# DigitalClockController.net
KiCad netlist of a schematic drawn in EAGLE
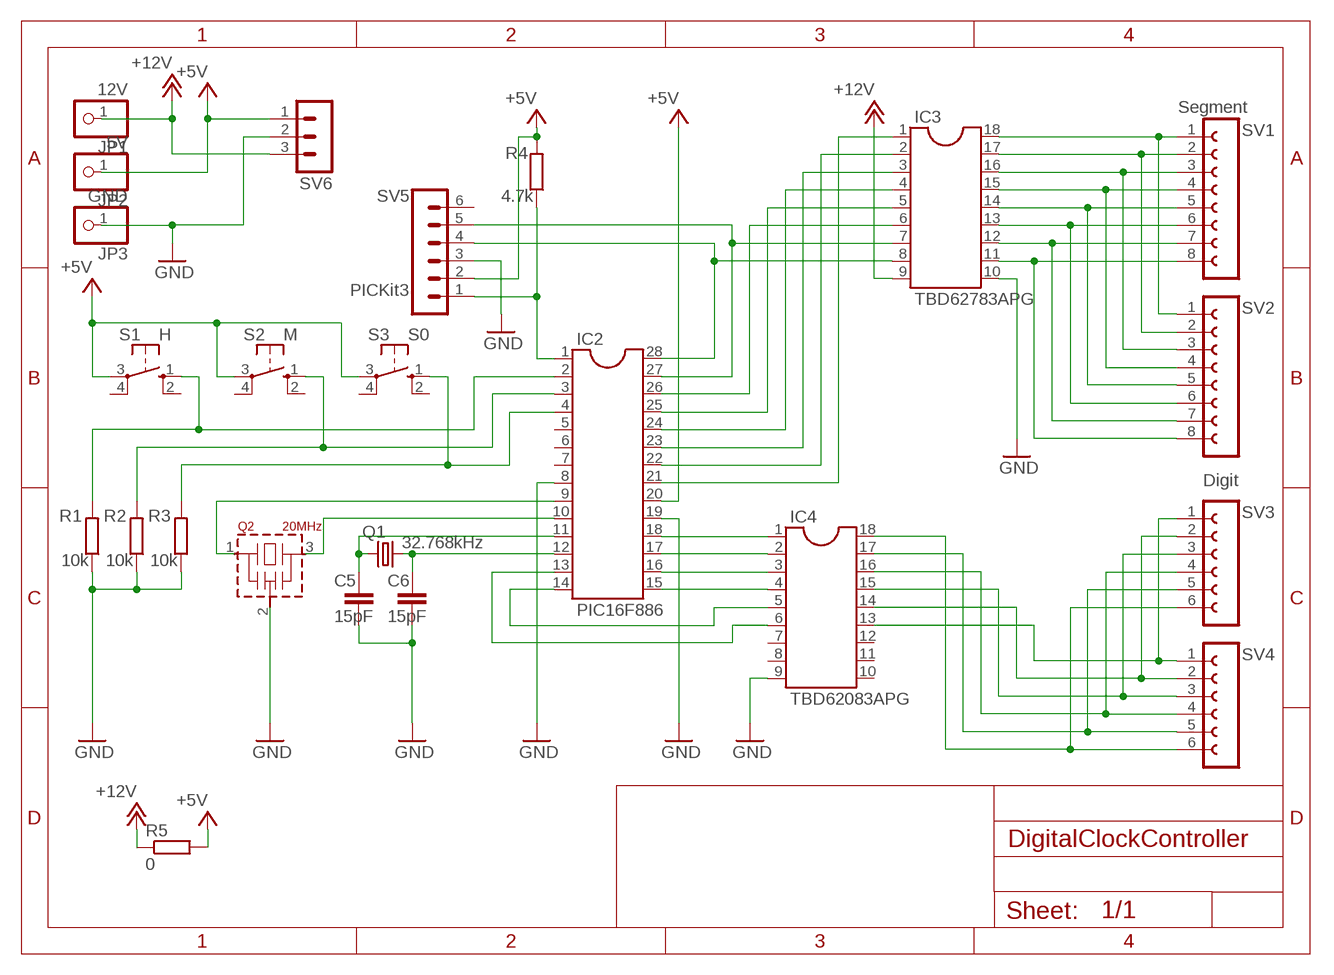
[diagram p0: schematic, sheet 1]

(export (version "E")
  (design (tool "Eeschema 10.0.6"))
  (components
    (comp (ref "C5")
      (value "15pF")
      (footprint "eagle-import:C025-024X044")
      (libsource (lib "eagle-import") (part "C-EU025-024X044"))
    )
    (comp (ref "C6")
      (value "15pF")
      (footprint "eagle-import:C025-024X044")
      (libsource (lib "eagle-import") (part "C-EU025-024X044"))
    )
    (comp (ref "IC2")
      (value "PIC16F886")
      (footprint "eagle-import:DIL28-3")
      (libsource (lib "eagle-import") (part "DIL28-3"))
    )
    (comp (ref "IC3")
      (value "TBD62783APG")
      (footprint "eagle-import:DIL18")
      (libsource (lib "eagle-import") (part "DIL18"))
    )
    (comp (ref "IC4")
      (value "TBD62083APG")
      (footprint "eagle-import:DIL18")
      (libsource (lib "eagle-import") (part "DIL18"))
    )
    (comp (ref "JP1")
      (value "12V")
      (footprint "eagle-import:1X01")
      (libsource (lib "eagle-import") (part "PINHD-1X1"))
    )
    (comp (ref "JP2")
      (value "5V")
      (footprint "eagle-import:1X01")
      (libsource (lib "eagle-import") (part "PINHD-1X1"))
    )
    (comp (ref "JP3")
      (value "GND")
      (footprint "eagle-import:1X01")
      (libsource (lib "eagle-import") (part "PINHD-1X1"))
    )
    (comp (ref "Q1")
      (value "32.768kHz")
      (footprint "eagle-import:TC26H")
      (libsource (lib "eagle-import") (part "CRYSTALTC26H"))
    )
    (comp (ref "Q2")
      (value "20MHz")
      (footprint "eagle-import:CSTLS_X")
      (libsource (lib "eagle-import") (part "CSTLS_X"))
    )
    (comp (ref "R1")
      (value "10k")
      (footprint "eagle-import:0207_10")
      (libsource (lib "eagle-import") (part "R-EU_0207/10"))
    )
    (comp (ref "R2")
      (value "10k")
      (footprint "eagle-import:0207_10")
      (libsource (lib "eagle-import") (part "R-EU_0207/10"))
    )
    (comp (ref "R3")
      (value "10k")
      (footprint "eagle-import:0207_10")
      (libsource (lib "eagle-import") (part "R-EU_0207/10"))
    )
    (comp (ref "R4")
      (value "4.7k")
      (footprint "eagle-import:0207_10")
      (libsource (lib "eagle-import") (part "R-EU_0207/10"))
    )
    (comp (ref "R5")
      (value "0")
      (footprint "eagle-import:0207_10")
      (libsource (lib "eagle-import") (part "R-EU_0207/10"))
    )
    (comp (ref "S1")
      (value "H")
      (footprint "eagle-import:B3F-10XX")
      (fields (field (name "MPN") "B3F-1000"))
      (libsource (lib "eagle-import") (part "10-XX"))
    )
    (comp (ref "S2")
      (value "M")
      (footprint "eagle-import:B3F-10XX")
      (fields (field (name "MPN") "B3F-1000"))
      (libsource (lib "eagle-import") (part "10-XX"))
    )
    (comp (ref "S3")
      (value "S0")
      (footprint "eagle-import:B3F-10XX")
      (fields (field (name "MPN") "B3F-1000"))
      (libsource (lib "eagle-import") (part "10-XX"))
    )
    (comp (ref "SV1")
      (value "Segment")
      (footprint "eagle-import:FE08")
      (libsource (lib "eagle-import") (part "FE08-1"))
    )
    (comp (ref "SV2")
      (value "Segment")
      (footprint "eagle-import:FE08")
      (libsource (lib "eagle-import") (part "FE08-1"))
    )
    (comp (ref "SV3")
      (value "Digit")
      (footprint "eagle-import:FE06")
      (libsource (lib "eagle-import") (part "FE06-1"))
    )
    (comp (ref "SV4")
      (value "Digit")
      (footprint "eagle-import:FE06")
      (libsource (lib "eagle-import") (part "FE06-1"))
    )
    (comp (ref "SV5")
      (value "PICKit3")
      (footprint "eagle-import:MA06-1")
      (libsource (lib "eagle-import") (part "MA06-1"))
    )
    (comp (ref "SV6")
      (value "MA03-1")
      (footprint "eagle-import:MA03-1")
      (libsource (lib "eagle-import") (part "MA03-1"))
    )
  )
  (nets
    (net (code "1") (name "+5V") (class "Default")
      (node (ref "IC2") (pin "20") (pinfunction "20_20") (pintype "passive"))
      (node (ref "JP2") (pin "1") (pinfunction "1_1") (pintype "passive"))
      (node (ref "R4") (pin "2") (pinfunction "2_2") (pintype "passive"))
      (node (ref "R5") (pin "2") (pinfunction "2_2") (pintype "passive"))
      (node (ref "S1") (pin "3") (pinfunction "P_3") (pintype "passive"))
      (node (ref "S2") (pin "3") (pinfunction "P_3") (pintype "passive"))
      (node (ref "S3") (pin "3") (pinfunction "P_3") (pintype "passive"))
      (node (ref "SV5") (pin "2") (pinfunction "2_2") (pintype "passive"))
      (node (ref "SV6") (pin "1") (pinfunction "1_1") (pintype "passive"))
    )
    (net (code "2") (name "+12V") (class "Default")
      (node (ref "IC3") (pin "9") (pinfunction "9_9") (pintype "passive"))
      (node (ref "JP1") (pin "1") (pinfunction "1_1") (pintype "passive"))
      (node (ref "R5") (pin "1") (pinfunction "1_1") (pintype "passive"))
      (node (ref "SV6") (pin "3") (pinfunction "3_3") (pintype "passive"))
    )
    (net (code "3") (name "GND") (class "Default")
      (node (ref "C5") (pin "2") (pinfunction "2_2") (pintype "passive"))
      (node (ref "C6") (pin "2") (pinfunction "2_2") (pintype "passive"))
      (node (ref "IC2") (pin "19") (pinfunction "19_19") (pintype "passive"))
      (node (ref "IC2") (pin "8") (pinfunction "8_8") (pintype "passive"))
      (node (ref "IC3") (pin "10") (pinfunction "10_10") (pintype "passive"))
      (node (ref "IC4") (pin "9") (pinfunction "9_9") (pintype "passive"))
      (node (ref "JP3") (pin "1") (pinfunction "1_1") (pintype "passive"))
      (node (ref "Q2") (pin "2") (pinfunction "VSS_2") (pintype "power_in"))
      (node (ref "R1") (pin "1") (pinfunction "1_1") (pintype "passive"))
      (node (ref "R2") (pin "1") (pinfunction "1_1") (pintype "passive"))
      (node (ref "R3") (pin "1") (pinfunction "1_1") (pintype "passive"))
      (node (ref "SV5") (pin "3") (pinfunction "3_3") (pintype "passive"))
      (node (ref "SV6") (pin "2") (pinfunction "2_2") (pintype "passive"))
    )
    (net (code "4") (name "Net-(C5-Pad1)") (class "Default")
      (node (ref "C5") (pin "1") (pinfunction "1_1") (pintype "passive"))
      (node (ref "IC2") (pin "11") (pinfunction "11_11") (pintype "passive"))
      (node (ref "Q1") (pin "2") (pinfunction "2_2") (pintype "passive"))
    )
    (net (code "5") (name "Net-(C6-Pad1)") (class "Default")
      (node (ref "C6") (pin "1") (pinfunction "1_1") (pintype "passive"))
      (node (ref "IC2") (pin "12") (pinfunction "12_12") (pintype "passive"))
      (node (ref "Q1") (pin "1") (pinfunction "1_1") (pintype "passive"))
    )
    (net (code "6") (name "Net-(IC2-Pad1)") (class "Default")
      (node (ref "IC2") (pin "1") (pinfunction "1_1") (pintype "passive"))
      (node (ref "R4") (pin "1") (pinfunction "1_1") (pintype "passive"))
      (node (ref "SV5") (pin "1") (pinfunction "1_1") (pintype "passive"))
    )
    (net (code "7") (name "Net-(IC2-Pad9)") (class "Default")
      (node (ref "IC2") (pin "9") (pinfunction "9_9") (pintype "passive"))
      (node (ref "Q2") (pin "1") (pinfunction "1_1") (pintype "output"))
    )
    (net (code "8") (name "Net-(IC2-Pad10)") (class "Default")
      (node (ref "IC2") (pin "10") (pinfunction "10_10") (pintype "passive"))
      (node (ref "Q2") (pin "3") (pinfunction "3_3") (pintype "input"))
    )
    (net (code "9") (name "Net-(IC2-Pad13)") (class "Default")
      (node (ref "IC2") (pin "13") (pinfunction "13_13") (pintype "passive"))
      (node (ref "IC4") (pin "6") (pinfunction "6_6") (pintype "passive"))
    )
    (net (code "10") (name "Net-(IC2-Pad14)") (class "Default")
      (node (ref "IC2") (pin "14") (pinfunction "14_14") (pintype "passive"))
      (node (ref "IC4") (pin "5") (pinfunction "5_5") (pintype "passive"))
    )
    (net (code "11") (name "Net-(IC2-Pad15)") (class "Default")
      (node (ref "IC2") (pin "15") (pinfunction "15_15") (pintype "passive"))
      (node (ref "IC4") (pin "4") (pinfunction "4_4") (pintype "passive"))
    )
    (net (code "12") (name "Net-(IC2-Pad16)") (class "Default")
      (node (ref "IC2") (pin "16") (pinfunction "16_16") (pintype "passive"))
      (node (ref "IC4") (pin "3") (pinfunction "3_3") (pintype "passive"))
    )
    (net (code "13") (name "Net-(IC2-Pad17)") (class "Default")
      (node (ref "IC2") (pin "17") (pinfunction "17_17") (pintype "passive"))
      (node (ref "IC4") (pin "2") (pinfunction "2_2") (pintype "passive"))
    )
    (net (code "14") (name "Net-(IC2-Pad18)") (class "Default")
      (node (ref "IC2") (pin "18") (pinfunction "18_18") (pintype "passive"))
      (node (ref "IC4") (pin "1") (pinfunction "1_1") (pintype "passive"))
    )
    (net (code "15") (name "Net-(IC2-Pad21)") (class "Default")
      (node (ref "IC2") (pin "21") (pinfunction "21_21") (pintype "passive"))
      (node (ref "IC3") (pin "1") (pinfunction "1_1") (pintype "passive"))
    )
    (net (code "16") (name "Net-(IC2-Pad22)") (class "Default")
      (node (ref "IC2") (pin "22") (pinfunction "22_22") (pintype "passive"))
      (node (ref "IC3") (pin "2") (pinfunction "2_2") (pintype "passive"))
    )
    (net (code "17") (name "Net-(IC2-Pad23)") (class "Default")
      (node (ref "IC2") (pin "23") (pinfunction "23_23") (pintype "passive"))
      (node (ref "IC3") (pin "3") (pinfunction "3_3") (pintype "passive"))
    )
    (net (code "18") (name "Net-(IC2-Pad24)") (class "Default")
      (node (ref "IC2") (pin "24") (pinfunction "24_24") (pintype "passive"))
      (node (ref "IC3") (pin "4") (pinfunction "4_4") (pintype "passive"))
    )
    (net (code "19") (name "Net-(IC2-Pad25)") (class "Default")
      (node (ref "IC2") (pin "25") (pinfunction "25_25") (pintype "passive"))
      (node (ref "IC3") (pin "5") (pinfunction "5_5") (pintype "passive"))
    )
    (net (code "20") (name "Net-(IC2-Pad26)") (class "Default")
      (node (ref "IC2") (pin "26") (pinfunction "26_26") (pintype "passive"))
      (node (ref "IC3") (pin "6") (pinfunction "6_6") (pintype "passive"))
    )
    (net (code "21") (name "Net-(IC2-Pad27)") (class "Default")
      (node (ref "IC2") (pin "27") (pinfunction "27_27") (pintype "passive"))
      (node (ref "IC3") (pin "7") (pinfunction "7_7") (pintype "passive"))
      (node (ref "SV5") (pin "5") (pinfunction "5_5") (pintype "passive"))
    )
    (net (code "22") (name "Net-(IC2-Pad28)") (class "Default")
      (node (ref "IC2") (pin "28") (pinfunction "28_28") (pintype "passive"))
      (node (ref "IC3") (pin "8") (pinfunction "8_8") (pintype "passive"))
      (node (ref "SV5") (pin "4") (pinfunction "4_4") (pintype "passive"))
    )
    (net (code "23") (name "Net-(IC3-Pad11)") (class "Default")
      (node (ref "IC3") (pin "11") (pinfunction "11_11") (pintype "passive"))
      (node (ref "SV1") (pin "8") (pinfunction "8_8") (pintype "passive"))
      (node (ref "SV2") (pin "8") (pinfunction "8_8") (pintype "passive"))
    )
    (net (code "24") (name "Net-(IC3-Pad12)") (class "Default")
      (node (ref "IC3") (pin "12") (pinfunction "12_12") (pintype "passive"))
      (node (ref "SV1") (pin "7") (pinfunction "7_7") (pintype "passive"))
      (node (ref "SV2") (pin "7") (pinfunction "7_7") (pintype "passive"))
    )
    (net (code "25") (name "Net-(IC3-Pad13)") (class "Default")
      (node (ref "IC3") (pin "13") (pinfunction "13_13") (pintype "passive"))
      (node (ref "SV1") (pin "6") (pinfunction "6_6") (pintype "passive"))
      (node (ref "SV2") (pin "6") (pinfunction "6_6") (pintype "passive"))
    )
    (net (code "26") (name "Net-(IC3-Pad14)") (class "Default")
      (node (ref "IC3") (pin "14") (pinfunction "14_14") (pintype "passive"))
      (node (ref "SV1") (pin "5") (pinfunction "5_5") (pintype "passive"))
      (node (ref "SV2") (pin "5") (pinfunction "5_5") (pintype "passive"))
    )
    (net (code "27") (name "Net-(IC3-Pad15)") (class "Default")
      (node (ref "IC3") (pin "15") (pinfunction "15_15") (pintype "passive"))
      (node (ref "SV1") (pin "4") (pinfunction "4_4") (pintype "passive"))
      (node (ref "SV2") (pin "4") (pinfunction "4_4") (pintype "passive"))
    )
    (net (code "28") (name "Net-(IC3-Pad16)") (class "Default")
      (node (ref "IC3") (pin "16") (pinfunction "16_16") (pintype "passive"))
      (node (ref "SV1") (pin "3") (pinfunction "3_3") (pintype "passive"))
      (node (ref "SV2") (pin "3") (pinfunction "3_3") (pintype "passive"))
    )
    (net (code "29") (name "Net-(IC3-Pad17)") (class "Default")
      (node (ref "IC3") (pin "17") (pinfunction "17_17") (pintype "passive"))
      (node (ref "SV1") (pin "2") (pinfunction "2_2") (pintype "passive"))
      (node (ref "SV2") (pin "2") (pinfunction "2_2") (pintype "passive"))
    )
    (net (code "30") (name "Net-(IC3-Pad18)") (class "Default")
      (node (ref "IC3") (pin "18") (pinfunction "18_18") (pintype "passive"))
      (node (ref "SV1") (pin "1") (pinfunction "1_1") (pintype "passive"))
      (node (ref "SV2") (pin "1") (pinfunction "1_1") (pintype "passive"))
    )
    (net (code "31") (name "Net-(IC4-Pad13)") (class "Default")
      (node (ref "IC4") (pin "13") (pinfunction "13_13") (pintype "passive"))
      (node (ref "SV3") (pin "1") (pinfunction "1_1") (pintype "passive"))
      (node (ref "SV4") (pin "1") (pinfunction "1_1") (pintype "passive"))
    )
    (net (code "32") (name "Net-(IC4-Pad14)") (class "Default")
      (node (ref "IC4") (pin "14") (pinfunction "14_14") (pintype "passive"))
      (node (ref "SV3") (pin "2") (pinfunction "2_2") (pintype "passive"))
      (node (ref "SV4") (pin "2") (pinfunction "2_2") (pintype "passive"))
    )
    (net (code "33") (name "Net-(IC4-Pad15)") (class "Default")
      (node (ref "IC4") (pin "15") (pinfunction "15_15") (pintype "passive"))
      (node (ref "SV3") (pin "3") (pinfunction "3_3") (pintype "passive"))
      (node (ref "SV4") (pin "3") (pinfunction "3_3") (pintype "passive"))
    )
    (net (code "34") (name "Net-(IC4-Pad16)") (class "Default")
      (node (ref "IC4") (pin "16") (pinfunction "16_16") (pintype "passive"))
      (node (ref "SV3") (pin "4") (pinfunction "4_4") (pintype "passive"))
      (node (ref "SV4") (pin "4") (pinfunction "4_4") (pintype "passive"))
    )
    (net (code "35") (name "Net-(IC4-Pad17)") (class "Default")
      (node (ref "IC4") (pin "17") (pinfunction "17_17") (pintype "passive"))
      (node (ref "SV3") (pin "5") (pinfunction "5_5") (pintype "passive"))
      (node (ref "SV4") (pin "5") (pinfunction "5_5") (pintype "passive"))
    )
    (net (code "36") (name "Net-(IC4-Pad18)") (class "Default")
      (node (ref "IC4") (pin "18") (pinfunction "18_18") (pintype "passive"))
      (node (ref "SV3") (pin "6") (pinfunction "6_6") (pintype "passive"))
      (node (ref "SV4") (pin "6") (pinfunction "6_6") (pintype "passive"))
    )
    (net (code "37") (name "Net-(S1-S)") (class "Default")
      (node (ref "IC2") (pin "2") (pinfunction "2_2") (pintype "passive"))
      (node (ref "R1") (pin "2") (pinfunction "2_2") (pintype "passive"))
      (node (ref "S1") (pin "1") (pinfunction "S_1") (pintype "passive"))
    )
    (net (code "38") (name "Net-(S2-S)") (class "Default")
      (node (ref "IC2") (pin "3") (pinfunction "3_3") (pintype "passive"))
      (node (ref "R2") (pin "2") (pinfunction "2_2") (pintype "passive"))
      (node (ref "S2") (pin "1") (pinfunction "S_1") (pintype "passive"))
    )
    (net (code "39") (name "Net-(S3-S)") (class "Default")
      (node (ref "IC2") (pin "4") (pinfunction "4_4") (pintype "passive"))
      (node (ref "R3") (pin "2") (pinfunction "2_2") (pintype "passive"))
      (node (ref "S3") (pin "1") (pinfunction "S_1") (pintype "passive"))
    )
    (net (code "40") (name "unconnected-(IC2-Pad5)") (class "Default")
      (node (ref "IC2") (pin "5") (pinfunction "5_5") (pintype "passive"))
    )
    (net (code "41") (name "unconnected-(IC2-Pad6)") (class "Default")
      (node (ref "IC2") (pin "6") (pinfunction "6_6") (pintype "passive"))
    )
    (net (code "42") (name "unconnected-(IC2-Pad7)") (class "Default")
      (node (ref "IC2") (pin "7") (pinfunction "7_7") (pintype "passive"))
    )
    (net (code "43") (name "unconnected-(IC4-Pad7)") (class "Default")
      (node (ref "IC4") (pin "7") (pinfunction "7_7") (pintype "passive"))
    )
    (net (code "44") (name "unconnected-(IC4-Pad8)") (class "Default")
      (node (ref "IC4") (pin "8") (pinfunction "8_8") (pintype "passive"))
    )
    (net (code "45") (name "unconnected-(IC4-Pad10)") (class "Default")
      (node (ref "IC4") (pin "10") (pinfunction "10_10") (pintype "passive"))
    )
    (net (code "46") (name "unconnected-(IC4-Pad11)") (class "Default")
      (node (ref "IC4") (pin "11") (pinfunction "11_11") (pintype "passive"))
    )
    (net (code "47") (name "unconnected-(IC4-Pad12)") (class "Default")
      (node (ref "IC4") (pin "12") (pinfunction "12_12") (pintype "passive"))
    )
    (net (code "48") (name "unconnected-(S1-P1-Pad4)") (class "Default")
      (node (ref "S1") (pin "4") (pinfunction "P1_4") (pintype "passive"))
    )
    (net (code "49") (name "unconnected-(S1-S1-Pad2)") (class "Default")
      (node (ref "S1") (pin "2") (pinfunction "S1_2") (pintype "passive"))
    )
    (net (code "50") (name "unconnected-(S2-P1-Pad4)") (class "Default")
      (node (ref "S2") (pin "4") (pinfunction "P1_4") (pintype "passive"))
    )
    (net (code "51") (name "unconnected-(S2-S1-Pad2)") (class "Default")
      (node (ref "S2") (pin "2") (pinfunction "S1_2") (pintype "passive"))
    )
    (net (code "52") (name "unconnected-(S3-P1-Pad4)") (class "Default")
      (node (ref "S3") (pin "4") (pinfunction "P1_4") (pintype "passive"))
    )
    (net (code "53") (name "unconnected-(S3-S1-Pad2)") (class "Default")
      (node (ref "S3") (pin "2") (pinfunction "S1_2") (pintype "passive"))
    )
    (net (code "54") (name "unconnected-(SV5-Pad6)") (class "Default")
      (node (ref "SV5") (pin "6") (pinfunction "6_6") (pintype "passive"))
    )
  )
)
